# Shift_register_2_IC_74595.net
KiCad netlist of a schematic drawn in EAGLE
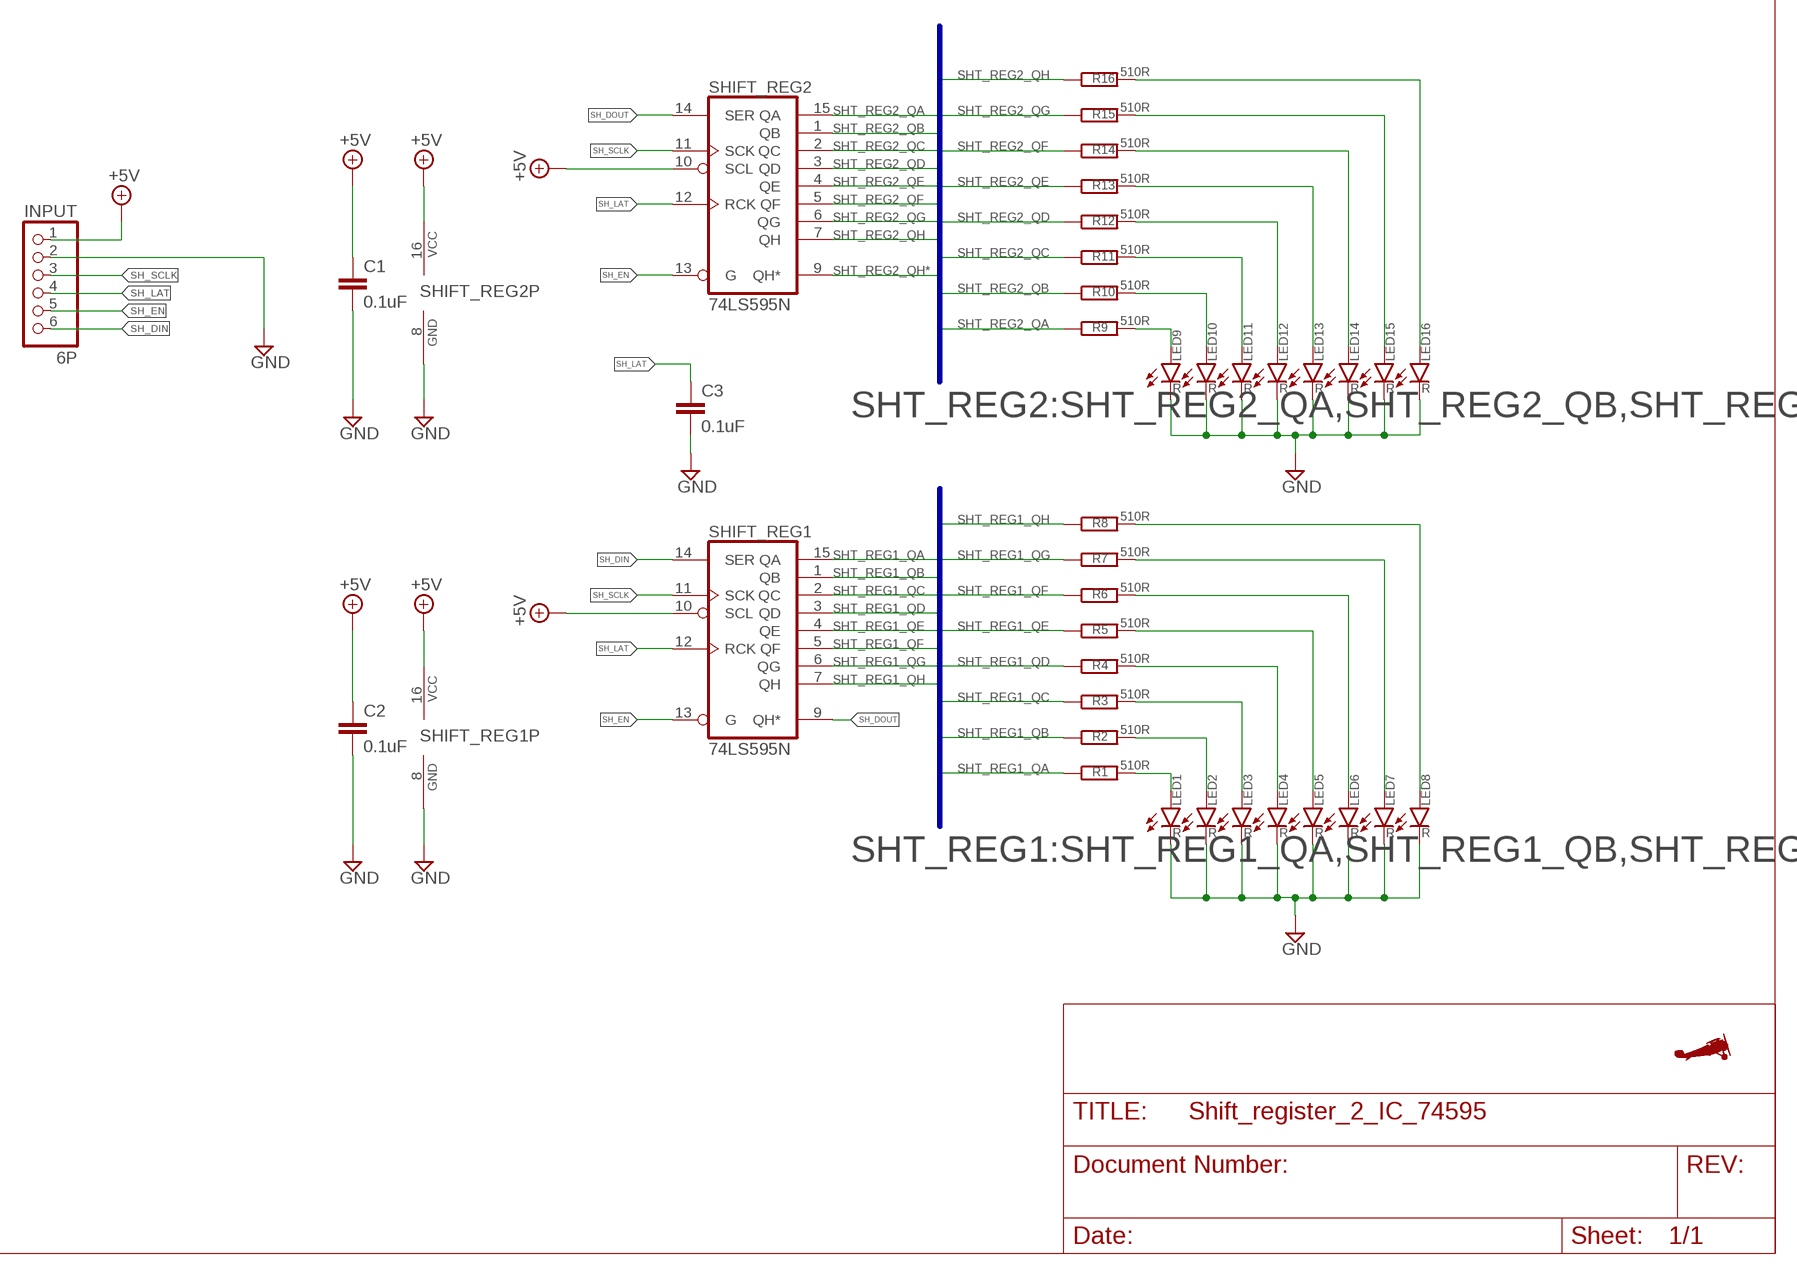
[diagram p0: schematic, sheet 1]

(export (version "E")
  (design (tool "Eeschema 10.0.6"))
  (components
    (comp (ref "C1")
      (value "0.1uF")
      (footprint "eagle-import:C050-030X075")
      (libsource (lib "eagle-import") (part "C-EU050-030X075"))
    )
    (comp (ref "C2")
      (value "0.1uF")
      (footprint "eagle-import:C050-030X075")
      (libsource (lib "eagle-import") (part "C-EU050-030X075"))
    )
    (comp (ref "C3")
      (value "0.1uF")
      (footprint "eagle-import:C050-030X075")
      (libsource (lib "eagle-import") (part "C-EU050-030X075"))
    )
    (comp (ref "INPUT")
      (value "6P")
      (footprint "eagle-import:1X06_90")
      (libsource (lib "eagle-import") (part "PINHD-1X6/90"))
    )
    (comp (ref "LED1")
      (value "R")
      (footprint "eagle-import:LED5MM")
      (libsource (lib "eagle-import") (part "LED5MM"))
    )
    (comp (ref "LED2")
      (value "R")
      (footprint "eagle-import:LED5MM")
      (libsource (lib "eagle-import") (part "LED5MM"))
    )
    (comp (ref "LED3")
      (value "R")
      (footprint "eagle-import:LED5MM")
      (libsource (lib "eagle-import") (part "LED5MM"))
    )
    (comp (ref "LED4")
      (value "R")
      (footprint "eagle-import:LED5MM")
      (libsource (lib "eagle-import") (part "LED5MM"))
    )
    (comp (ref "LED5")
      (value "R")
      (footprint "eagle-import:LED5MM")
      (libsource (lib "eagle-import") (part "LED5MM"))
    )
    (comp (ref "LED6")
      (value "R")
      (footprint "eagle-import:LED5MM")
      (libsource (lib "eagle-import") (part "LED5MM"))
    )
    (comp (ref "LED7")
      (value "R")
      (footprint "eagle-import:LED5MM")
      (libsource (lib "eagle-import") (part "LED5MM"))
    )
    (comp (ref "LED8")
      (value "R")
      (footprint "eagle-import:LED5MM")
      (libsource (lib "eagle-import") (part "LED5MM"))
    )
    (comp (ref "LED9")
      (value "R")
      (footprint "eagle-import:LED5MM")
      (libsource (lib "eagle-import") (part "LED5MM"))
    )
    (comp (ref "LED10")
      (value "R")
      (footprint "eagle-import:LED5MM")
      (libsource (lib "eagle-import") (part "LED5MM"))
    )
    (comp (ref "LED11")
      (value "R")
      (footprint "eagle-import:LED5MM")
      (libsource (lib "eagle-import") (part "LED5MM"))
    )
    (comp (ref "LED12")
      (value "R")
      (footprint "eagle-import:LED5MM")
      (libsource (lib "eagle-import") (part "LED5MM"))
    )
    (comp (ref "LED13")
      (value "R")
      (footprint "eagle-import:LED5MM")
      (libsource (lib "eagle-import") (part "LED5MM"))
    )
    (comp (ref "LED14")
      (value "R")
      (footprint "eagle-import:LED5MM")
      (libsource (lib "eagle-import") (part "LED5MM"))
    )
    (comp (ref "LED15")
      (value "R")
      (footprint "eagle-import:LED5MM")
      (libsource (lib "eagle-import") (part "LED5MM"))
    )
    (comp (ref "LED16")
      (value "R")
      (footprint "eagle-import:LED5MM")
      (libsource (lib "eagle-import") (part "LED5MM"))
    )
    (comp (ref "R1")
      (value "510R")
      (footprint "eagle-import:0207_10")
      (libsource (lib "eagle-import") (part "R-EU_0207/10"))
    )
    (comp (ref "R2")
      (value "510R")
      (footprint "eagle-import:0207_10")
      (libsource (lib "eagle-import") (part "R-EU_0207/10"))
    )
    (comp (ref "R3")
      (value "510R")
      (footprint "eagle-import:0207_10")
      (libsource (lib "eagle-import") (part "R-EU_0207/10"))
    )
    (comp (ref "R4")
      (value "510R")
      (footprint "eagle-import:0207_10")
      (libsource (lib "eagle-import") (part "R-EU_0207/10"))
    )
    (comp (ref "R5")
      (value "510R")
      (footprint "eagle-import:0207_10")
      (libsource (lib "eagle-import") (part "R-EU_0207/10"))
    )
    (comp (ref "R6")
      (value "510R")
      (footprint "eagle-import:0207_10")
      (libsource (lib "eagle-import") (part "R-EU_0207/10"))
    )
    (comp (ref "R7")
      (value "510R")
      (footprint "eagle-import:0207_10")
      (libsource (lib "eagle-import") (part "R-EU_0207/10"))
    )
    (comp (ref "R8")
      (value "510R")
      (footprint "eagle-import:0207_10")
      (libsource (lib "eagle-import") (part "R-EU_0207/10"))
    )
    (comp (ref "R9")
      (value "510R")
      (footprint "eagle-import:0207_10")
      (libsource (lib "eagle-import") (part "R-EU_0207/10"))
    )
    (comp (ref "R10")
      (value "510R")
      (footprint "eagle-import:0207_10")
      (libsource (lib "eagle-import") (part "R-EU_0207/10"))
    )
    (comp (ref "R11")
      (value "510R")
      (footprint "eagle-import:0207_10")
      (libsource (lib "eagle-import") (part "R-EU_0207/10"))
    )
    (comp (ref "R12")
      (value "510R")
      (footprint "eagle-import:0207_10")
      (libsource (lib "eagle-import") (part "R-EU_0207/10"))
    )
    (comp (ref "R13")
      (value "510R")
      (footprint "eagle-import:0207_10")
      (libsource (lib "eagle-import") (part "R-EU_0207/10"))
    )
    (comp (ref "R14")
      (value "510R")
      (footprint "eagle-import:0207_10")
      (libsource (lib "eagle-import") (part "R-EU_0207/10"))
    )
    (comp (ref "R15")
      (value "510R")
      (footprint "eagle-import:0207_10")
      (libsource (lib "eagle-import") (part "R-EU_0207/10"))
    )
    (comp (ref "R16")
      (value "510R")
      (footprint "eagle-import:0207_10")
      (libsource (lib "eagle-import") (part "R-EU_0207/10"))
    )
    (comp (ref "SHIFT_REG1")
      (value "74LS595N")
      (footprint "eagle-import:DIL16")
      (libsource (lib "eagle-import") (part "74595NLS"))
    )
    (comp (ref "SHIFT_REG2")
      (value "74LS595N")
      (footprint "eagle-import:DIL16")
      (libsource (lib "eagle-import") (part "74595NLS"))
    )
    (comp (ref "U$1")
      (value "AIRPLANE")
      (footprint "eagle-import:AIRPLANE_MEDIUM")
      (libsource (lib "eagle-import") (part "AIRPLANE"))
    )
  )
  (nets
    (net (code "4") (name "+5V") (class "Default")
      (node (ref "C1") (pin "1") (pinfunction "1_1") (pintype "passive"))
      (node (ref "C2") (pin "1") (pinfunction "1_1") (pintype "passive"))
      (node (ref "INPUT") (pin "1") (pinfunction "1_1") (pintype "passive"))
      (node (ref "SHIFT_REG1") (pin "10") (pinfunction "SCL_10") (pintype "input"))
      (node (ref "SHIFT_REG1") (pin "16") (pinfunction "VCC_16") (pintype "power_in"))
      (node (ref "SHIFT_REG2") (pin "10") (pinfunction "SCL_10") (pintype "input"))
      (node (ref "SHIFT_REG2") (pin "16") (pinfunction "VCC_16") (pintype "power_in"))
    )
    (net (code "5") (name "/SHT_REG1_QA") (class "Default")
      (node (ref "R1") (pin "1") (pinfunction "1_1") (pintype "passive"))
      (node (ref "SHIFT_REG1") (pin "15") (pinfunction "QA_15") (pintype "tri_state"))
    )
    (net (code "6") (name "/SHT_REG1_QB") (class "Default")
      (node (ref "R2") (pin "1") (pinfunction "1_1") (pintype "passive"))
      (node (ref "SHIFT_REG1") (pin "1") (pinfunction "QB_1") (pintype "tri_state"))
    )
    (net (code "7") (name "/SHT_REG1_QC") (class "Default")
      (node (ref "R3") (pin "1") (pinfunction "1_1") (pintype "passive"))
      (node (ref "SHIFT_REG1") (pin "2") (pinfunction "QC_2") (pintype "tri_state"))
    )
    (net (code "8") (name "/SHT_REG1_QD") (class "Default")
      (node (ref "R4") (pin "1") (pinfunction "1_1") (pintype "passive"))
      (node (ref "SHIFT_REG1") (pin "3") (pinfunction "QD_3") (pintype "tri_state"))
    )
    (net (code "9") (name "/SHT_REG1_QE") (class "Default")
      (node (ref "R5") (pin "1") (pinfunction "1_1") (pintype "passive"))
      (node (ref "SHIFT_REG1") (pin "4") (pinfunction "QE_4") (pintype "tri_state"))
    )
    (net (code "10") (name "/SHT_REG1_QF") (class "Default")
      (node (ref "R6") (pin "1") (pinfunction "1_1") (pintype "passive"))
      (node (ref "SHIFT_REG1") (pin "5") (pinfunction "QF_5") (pintype "tri_state"))
    )
    (net (code "11") (name "/SHT_REG1_QG") (class "Default")
      (node (ref "R7") (pin "1") (pinfunction "1_1") (pintype "passive"))
      (node (ref "SHIFT_REG1") (pin "6") (pinfunction "QG_6") (pintype "tri_state"))
    )
    (net (code "12") (name "/SHT_REG1_QH") (class "Default")
      (node (ref "R8") (pin "1") (pinfunction "1_1") (pintype "passive"))
      (node (ref "SHIFT_REG1") (pin "7") (pinfunction "QH_7") (pintype "tri_state"))
    )
    (net (code "13") (name "/SHT_REG2_QA") (class "Default")
      (node (ref "R9") (pin "1") (pinfunction "1_1") (pintype "passive"))
      (node (ref "SHIFT_REG2") (pin "15") (pinfunction "QA_15") (pintype "tri_state"))
    )
    (net (code "14") (name "/SHT_REG2_QB") (class "Default")
      (node (ref "R10") (pin "1") (pinfunction "1_1") (pintype "passive"))
      (node (ref "SHIFT_REG2") (pin "1") (pinfunction "QB_1") (pintype "tri_state"))
    )
    (net (code "15") (name "/SHT_REG2_QC") (class "Default")
      (node (ref "R11") (pin "1") (pinfunction "1_1") (pintype "passive"))
      (node (ref "SHIFT_REG2") (pin "2") (pinfunction "QC_2") (pintype "tri_state"))
    )
    (net (code "16") (name "/SHT_REG2_QD") (class "Default")
      (node (ref "R12") (pin "1") (pinfunction "1_1") (pintype "passive"))
      (node (ref "SHIFT_REG2") (pin "3") (pinfunction "QD_3") (pintype "tri_state"))
    )
    (net (code "17") (name "/SHT_REG2_QE") (class "Default")
      (node (ref "R13") (pin "1") (pinfunction "1_1") (pintype "passive"))
      (node (ref "SHIFT_REG2") (pin "4") (pinfunction "QE_4") (pintype "tri_state"))
    )
    (net (code "18") (name "/SHT_REG2_QF") (class "Default")
      (node (ref "R14") (pin "1") (pinfunction "1_1") (pintype "passive"))
      (node (ref "SHIFT_REG2") (pin "5") (pinfunction "QF_5") (pintype "tri_state"))
    )
    (net (code "19") (name "/SHT_REG2_QG") (class "Default")
      (node (ref "R15") (pin "1") (pinfunction "1_1") (pintype "passive"))
      (node (ref "SHIFT_REG2") (pin "6") (pinfunction "QG_6") (pintype "tri_state"))
    )
    (net (code "20") (name "/SHT_REG2_QH") (class "Default")
      (node (ref "R16") (pin "1") (pinfunction "1_1") (pintype "passive"))
      (node (ref "SHIFT_REG2") (pin "7") (pinfunction "QH_7") (pintype "tri_state"))
    )
    (net (code "21") (name "/SHT_REG2_QH*") (class "Default")
      (node (ref "SHIFT_REG2") (pin "9") (pinfunction "QH*_9") (pintype "tri_state"))
    )
    (net (code "24") (name "GND") (class "Default")
      (node (ref "C1") (pin "2") (pinfunction "2_2") (pintype "passive"))
      (node (ref "C2") (pin "2") (pinfunction "2_2") (pintype "passive"))
      (node (ref "C3") (pin "2") (pinfunction "2_2") (pintype "passive"))
      (node (ref "INPUT") (pin "2") (pinfunction "2_2") (pintype "passive"))
      (node (ref "LED1") (pin "K") (pinfunction "C_K") (pintype "passive"))
      (node (ref "LED10") (pin "K") (pinfunction "C_K") (pintype "passive"))
      (node (ref "LED11") (pin "K") (pinfunction "C_K") (pintype "passive"))
      (node (ref "LED12") (pin "K") (pinfunction "C_K") (pintype "passive"))
      (node (ref "LED13") (pin "K") (pinfunction "C_K") (pintype "passive"))
      (node (ref "LED14") (pin "K") (pinfunction "C_K") (pintype "passive"))
      (node (ref "LED15") (pin "K") (pinfunction "C_K") (pintype "passive"))
      (node (ref "LED16") (pin "K") (pinfunction "C_K") (pintype "passive"))
      (node (ref "LED2") (pin "K") (pinfunction "C_K") (pintype "passive"))
      (node (ref "LED3") (pin "K") (pinfunction "C_K") (pintype "passive"))
      (node (ref "LED4") (pin "K") (pinfunction "C_K") (pintype "passive"))
      (node (ref "LED5") (pin "K") (pinfunction "C_K") (pintype "passive"))
      (node (ref "LED6") (pin "K") (pinfunction "C_K") (pintype "passive"))
      (node (ref "LED7") (pin "K") (pinfunction "C_K") (pintype "passive"))
      (node (ref "LED8") (pin "K") (pinfunction "C_K") (pintype "passive"))
      (node (ref "LED9") (pin "K") (pinfunction "C_K") (pintype "passive"))
      (node (ref "SHIFT_REG1") (pin "8") (pinfunction "GND_8") (pintype "power_in"))
      (node (ref "SHIFT_REG2") (pin "8") (pinfunction "GND_8") (pintype "power_in"))
    )
    (net (code "25") (name "Net-(LED1-PadA)") (class "Default")
      (node (ref "LED1") (pin "A") (pinfunction "A_A") (pintype "passive"))
      (node (ref "R1") (pin "2") (pinfunction "2_2") (pintype "passive"))
    )
    (net (code "26") (name "Net-(LED2-PadA)") (class "Default")
      (node (ref "LED2") (pin "A") (pinfunction "A_A") (pintype "passive"))
      (node (ref "R2") (pin "2") (pinfunction "2_2") (pintype "passive"))
    )
    (net (code "27") (name "Net-(LED3-PadA)") (class "Default")
      (node (ref "LED3") (pin "A") (pinfunction "A_A") (pintype "passive"))
      (node (ref "R3") (pin "2") (pinfunction "2_2") (pintype "passive"))
    )
    (net (code "28") (name "Net-(LED4-PadA)") (class "Default")
      (node (ref "LED4") (pin "A") (pinfunction "A_A") (pintype "passive"))
      (node (ref "R4") (pin "2") (pinfunction "2_2") (pintype "passive"))
    )
    (net (code "29") (name "Net-(LED5-PadA)") (class "Default")
      (node (ref "LED5") (pin "A") (pinfunction "A_A") (pintype "passive"))
      (node (ref "R5") (pin "2") (pinfunction "2_2") (pintype "passive"))
    )
    (net (code "30") (name "Net-(LED6-PadA)") (class "Default")
      (node (ref "LED6") (pin "A") (pinfunction "A_A") (pintype "passive"))
      (node (ref "R6") (pin "2") (pinfunction "2_2") (pintype "passive"))
    )
    (net (code "31") (name "Net-(LED7-PadA)") (class "Default")
      (node (ref "LED7") (pin "A") (pinfunction "A_A") (pintype "passive"))
      (node (ref "R7") (pin "2") (pinfunction "2_2") (pintype "passive"))
    )
    (net (code "32") (name "Net-(LED8-PadA)") (class "Default")
      (node (ref "LED8") (pin "A") (pinfunction "A_A") (pintype "passive"))
      (node (ref "R8") (pin "2") (pinfunction "2_2") (pintype "passive"))
    )
    (net (code "33") (name "Net-(LED9-PadA)") (class "Default")
      (node (ref "LED9") (pin "A") (pinfunction "A_A") (pintype "passive"))
      (node (ref "R9") (pin "2") (pinfunction "2_2") (pintype "passive"))
    )
    (net (code "34") (name "Net-(LED10-PadA)") (class "Default")
      (node (ref "LED10") (pin "A") (pinfunction "A_A") (pintype "passive"))
      (node (ref "R10") (pin "2") (pinfunction "2_2") (pintype "passive"))
    )
    (net (code "35") (name "Net-(LED11-PadA)") (class "Default")
      (node (ref "LED11") (pin "A") (pinfunction "A_A") (pintype "passive"))
      (node (ref "R11") (pin "2") (pinfunction "2_2") (pintype "passive"))
    )
    (net (code "36") (name "Net-(LED12-PadA)") (class "Default")
      (node (ref "LED12") (pin "A") (pinfunction "A_A") (pintype "passive"))
      (node (ref "R12") (pin "2") (pinfunction "2_2") (pintype "passive"))
    )
    (net (code "37") (name "Net-(LED13-PadA)") (class "Default")
      (node (ref "LED13") (pin "A") (pinfunction "A_A") (pintype "passive"))
      (node (ref "R13") (pin "2") (pinfunction "2_2") (pintype "passive"))
    )
    (net (code "38") (name "Net-(LED14-PadA)") (class "Default")
      (node (ref "LED14") (pin "A") (pinfunction "A_A") (pintype "passive"))
      (node (ref "R14") (pin "2") (pinfunction "2_2") (pintype "passive"))
    )
    (net (code "39") (name "Net-(LED15-PadA)") (class "Default")
      (node (ref "LED15") (pin "A") (pinfunction "A_A") (pintype "passive"))
      (node (ref "R15") (pin "2") (pinfunction "2_2") (pintype "passive"))
    )
    (net (code "40") (name "Net-(LED16-PadA)") (class "Default")
      (node (ref "LED16") (pin "A") (pinfunction "A_A") (pintype "passive"))
      (node (ref "R16") (pin "2") (pinfunction "2_2") (pintype "passive"))
    )
    (net (code "41") (name "SH_DIN") (class "Default")
      (node (ref "INPUT") (pin "6") (pinfunction "6_6") (pintype "passive"))
      (node (ref "SHIFT_REG1") (pin "14") (pinfunction "SER_14") (pintype "input"))
    )
    (net (code "42") (name "SH_DOUT") (class "Default")
      (node (ref "SHIFT_REG1") (pin "9") (pinfunction "QH*_9") (pintype "tri_state"))
      (node (ref "SHIFT_REG2") (pin "14") (pinfunction "SER_14") (pintype "input"))
    )
    (net (code "43") (name "SH_EN") (class "Default")
      (node (ref "INPUT") (pin "5") (pinfunction "5_5") (pintype "passive"))
      (node (ref "SHIFT_REG1") (pin "13") (pinfunction "G_13") (pintype "input"))
      (node (ref "SHIFT_REG2") (pin "13") (pinfunction "G_13") (pintype "input"))
    )
    (net (code "44") (name "SH_LAT") (class "Default")
      (node (ref "C3") (pin "1") (pinfunction "1_1") (pintype "passive"))
      (node (ref "INPUT") (pin "4") (pinfunction "4_4") (pintype "passive"))
      (node (ref "SHIFT_REG1") (pin "12") (pinfunction "RCK_12") (pintype "input"))
      (node (ref "SHIFT_REG2") (pin "12") (pinfunction "RCK_12") (pintype "input"))
    )
    (net (code "45") (name "SH_SCLK") (class "Default")
      (node (ref "INPUT") (pin "3") (pinfunction "3_3") (pintype "passive"))
      (node (ref "SHIFT_REG1") (pin "11") (pinfunction "SCK_11") (pintype "input"))
      (node (ref "SHIFT_REG2") (pin "11") (pinfunction "SCK_11") (pintype "input"))
    )
  )
)
